# IO.net
KiCad netlist of a schematic drawn in Altium Designer
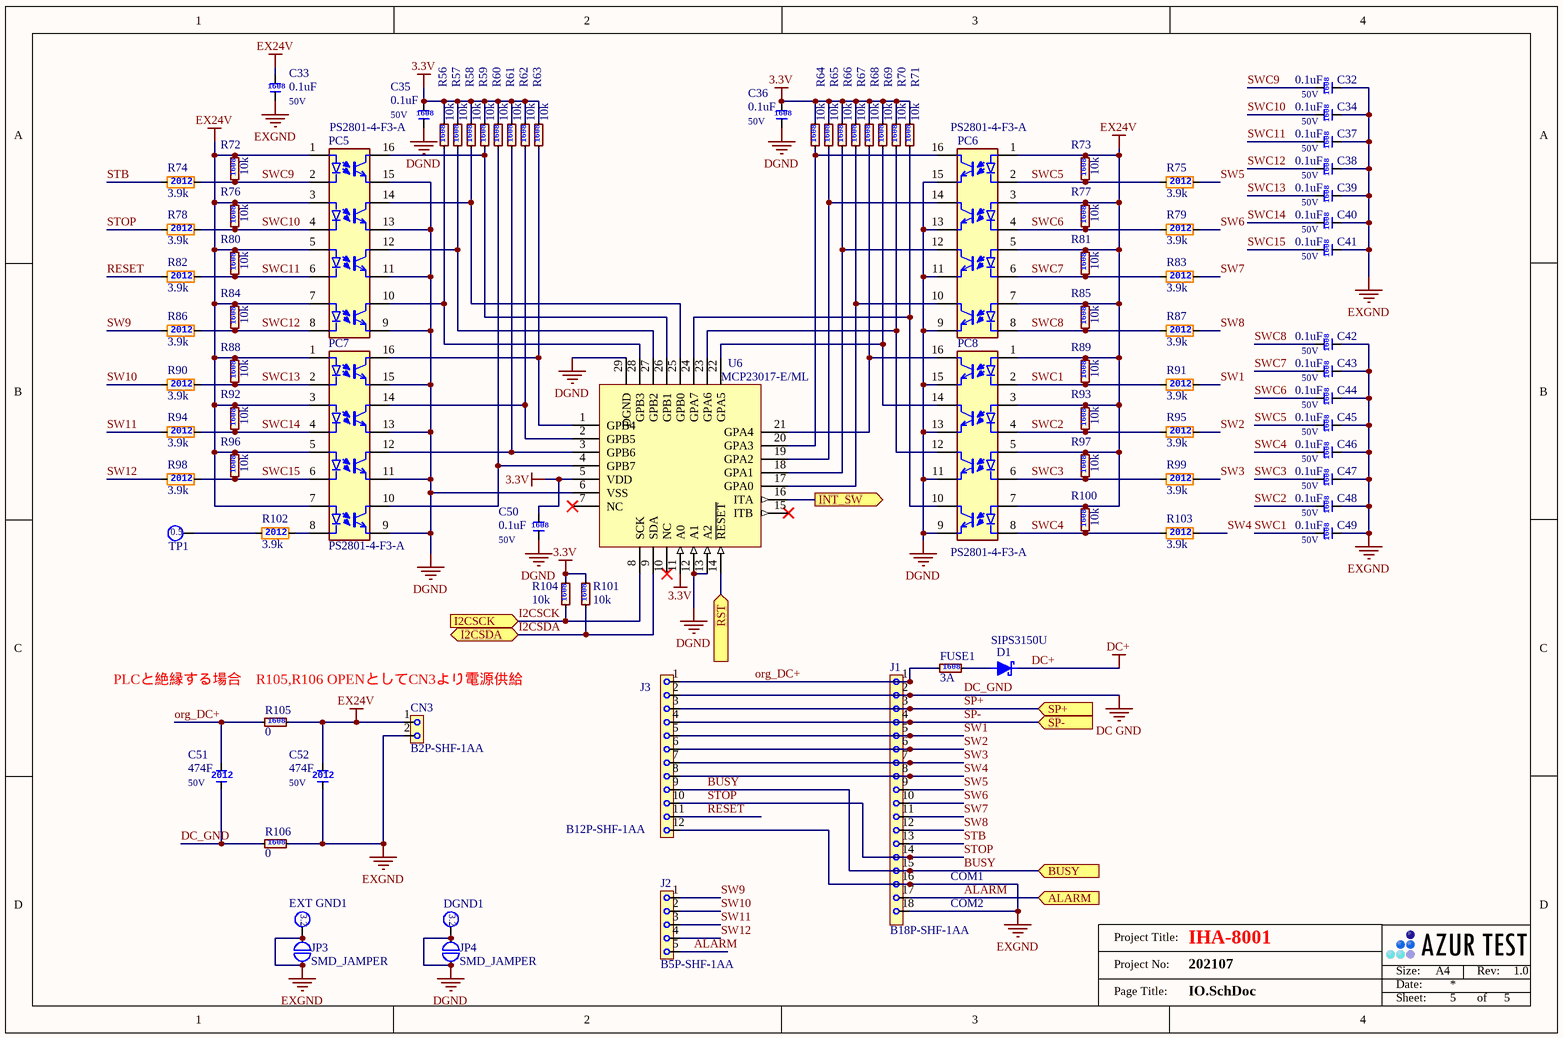
[diagram p0: IO.SchDoc]

(export (version "E")
  (design (tool "Eeschema 10.0.6"))
  (components
    (comp (ref "C32")
      (value "CGA3E2X7R1H104K080AA")
      (footprint "C1608")
      (description "セラコン1608サイズ")
      (fields (field (name "TAG") "0.1uF") (field (name "VOLTAGE") "50V"))
      (libsource (lib "Audio Prj") (part "C1608"))
    )
    (comp (ref "C33")
      (value "CGA3E2X7R1H104K080AA")
      (footprint "C1608")
      (description "セラコン1608サイズ")
      (fields (field (name "TAG") "0.1uF") (field (name "VOLTAGE") "50V"))
      (libsource (lib "Audio Prj") (part "C1608"))
    )
    (comp (ref "C34")
      (value "CGA3E2X7R1H104K080AA")
      (footprint "C1608")
      (description "セラコン1608サイズ")
      (fields (field (name "TAG") "0.1uF") (field (name "VOLTAGE") "50V"))
      (libsource (lib "Audio Prj") (part "C1608"))
    )
    (comp (ref "C35")
      (value "CGA3E2X7R1H104K080AA")
      (footprint "C1608")
      (description "セラコン1608サイズ")
      (fields (field (name "TAG") "0.1uF") (field (name "VOLTAGE") "50V"))
      (libsource (lib "Audio Prj") (part "C1608"))
    )
    (comp (ref "C36")
      (value "CGA3E2X7R1H104K080AA")
      (footprint "C1608")
      (description "セラコン1608サイズ")
      (fields (field (name "TAG") "0.1uF") (field (name "VOLTAGE") "50V"))
      (libsource (lib "Audio Prj") (part "C1608"))
    )
    (comp (ref "C37")
      (value "CGA3E2X7R1H104K080AA")
      (footprint "C1608")
      (description "セラコン1608サイズ")
      (fields (field (name "TAG") "0.1uF") (field (name "VOLTAGE") "50V"))
      (libsource (lib "Audio Prj") (part "C1608"))
    )
    (comp (ref "C38")
      (value "CGA3E2X7R1H104K080AA")
      (footprint "C1608")
      (description "セラコン1608サイズ")
      (fields (field (name "TAG") "0.1uF") (field (name "VOLTAGE") "50V"))
      (libsource (lib "Audio Prj") (part "C1608"))
    )
    (comp (ref "C39")
      (value "CGA3E2X7R1H104K080AA")
      (footprint "C1608")
      (description "セラコン1608サイズ")
      (fields (field (name "TAG") "0.1uF") (field (name "VOLTAGE") "50V"))
      (libsource (lib "Audio Prj") (part "C1608"))
    )
    (comp (ref "C40")
      (value "CGA3E2X7R1H104K080AA")
      (footprint "C1608")
      (description "セラコン1608サイズ")
      (fields (field (name "TAG") "0.1uF") (field (name "VOLTAGE") "50V"))
      (libsource (lib "Audio Prj") (part "C1608"))
    )
    (comp (ref "C41")
      (value "CGA3E2X7R1H104K080AA")
      (footprint "C1608")
      (description "セラコン1608サイズ")
      (fields (field (name "TAG") "0.1uF") (field (name "VOLTAGE") "50V"))
      (libsource (lib "Audio Prj") (part "C1608"))
    )
    (comp (ref "C42")
      (value "CGA3E2X7R1H104K080AA")
      (footprint "C1608")
      (description "セラコン1608サイズ")
      (fields (field (name "TAG") "0.1uF") (field (name "VOLTAGE") "50V"))
      (libsource (lib "Audio Prj") (part "C1608"))
    )
    (comp (ref "C43")
      (value "CGA3E2X7R1H104K080AA")
      (footprint "C1608")
      (description "セラコン1608サイズ")
      (fields (field (name "TAG") "0.1uF") (field (name "VOLTAGE") "50V"))
      (libsource (lib "Audio Prj") (part "C1608"))
    )
    (comp (ref "C44")
      (value "CGA3E2X7R1H104K080AA")
      (footprint "C1608")
      (description "セラコン1608サイズ")
      (fields (field (name "TAG") "0.1uF") (field (name "VOLTAGE") "50V"))
      (libsource (lib "Audio Prj") (part "C1608"))
    )
    (comp (ref "C45")
      (value "CGA3E2X7R1H104K080AA")
      (footprint "C1608")
      (description "セラコン1608サイズ")
      (fields (field (name "TAG") "0.1uF") (field (name "VOLTAGE") "50V"))
      (libsource (lib "Audio Prj") (part "C1608"))
    )
    (comp (ref "C46")
      (value "CGA3E2X7R1H104K080AA")
      (footprint "C1608")
      (description "セラコン1608サイズ")
      (fields (field (name "TAG") "0.1uF") (field (name "VOLTAGE") "50V"))
      (libsource (lib "Audio Prj") (part "C1608"))
    )
    (comp (ref "C47")
      (value "CGA3E2X7R1H104K080AA")
      (footprint "C1608")
      (description "セラコン1608サイズ")
      (fields (field (name "TAG") "0.1uF") (field (name "VOLTAGE") "50V"))
      (libsource (lib "Audio Prj") (part "C1608"))
    )
    (comp (ref "C48")
      (value "CGA3E2X7R1H104K080AA")
      (footprint "C1608")
      (description "セラコン1608サイズ")
      (fields (field (name "TAG") "0.1uF") (field (name "VOLTAGE") "50V"))
      (libsource (lib "Audio Prj") (part "C1608"))
    )
    (comp (ref "C49")
      (value "CGA3E2X7R1H104K080AA")
      (footprint "C1608")
      (description "セラコン1608サイズ")
      (fields (field (name "TAG") "0.1uF") (field (name "VOLTAGE") "50V"))
      (libsource (lib "Audio Prj") (part "C1608"))
    )
    (comp (ref "C50")
      (value "CGA3E2X7R1H104K080AA")
      (footprint "C1608")
      (description "セラコン1608サイズ")
      (fields (field (name "TAG") "0.1uF") (field (name "VOLTAGE") "50V"))
      (libsource (lib "Audio Prj") (part "C1608"))
    )
    (comp (ref "C51")
      (value "GRM21BR71H474MA88")
      (footprint "C2012")
      (description "セラコン2012サイズ")
      (fields (field (name "TAG") "474F") (field (name "VOLTAGE") "50V"))
      (libsource (lib "Audio Prj") (part "C2012"))
    )
    (comp (ref "C52")
      (value "GRM21BR71H474MA88")
      (footprint "C2012")
      (description "セラコン2012サイズ")
      (fields (field (name "TAG") "474F") (field (name "VOLTAGE") "50V"))
      (libsource (lib "Audio Prj") (part "C2012"))
    )
    (comp (ref "CN3")
      (value "B2P-SHF-1AA")
      (footprint "B2P-SHF-1AA")
      (description "雄,ストレート,1列2ピン")
      (libsource (lib "Audio Prj") (part "B2P-SHF-1AA"))
    )
    (comp (ref "D1")
      (value "SIPS3150U")
      (footprint "DO-214AA")
      (description "Schottky Rectifier")
      (fields (field (name "VOLTAGE") "150V"))
      (libsource (lib "Audio Prj") (part "Diode SMB 5.4x4.3"))
    )
    (comp (ref "DGND1")
      (value "TP3.2mm")
      (footprint "TP3.2mm")
      (description "Test-Point 3.2mm")
      (libsource (lib "Audio Prj") (part "TP3.2mm"))
    )
    (comp (ref "EXT GND1")
      (value "TP3.2mm")
      (footprint "TP3.2mm")
      (description "Test-Point 3.2mm")
      (libsource (lib "Audio Prj") (part "TP3.2mm"))
    )
    (comp (ref "FUSE1")
      (value "ERB-RE3R00V")
      (footprint "R1608")
      (description "3A 1608サイズ")
      (fields (field (name "TAG") "3A"))
      (libsource (lib "") (part "TF1608_1"))
    )
    (comp (ref "J1")
      (value "B18P-SHF-1AA")
      (footprint "B18P-SHF-1AA")
      (description "雄,ストレート,1列12ピン PCB")
      (libsource (lib "Audio Prj") (part "B18P-SHF-1AA"))
    )
    (comp (ref "J2")
      (value "B5P-SHF-1AA")
      (footprint "B5P-SHF-1AA")
      (description "雄,ストレート,1列3ピン")
      (libsource (lib "Audio Prj") (part "B5P-SHF-1AA"))
    )
    (comp (ref "J3")
      (value "B12P-SHF-1AA")
      (footprint "B12P-SHF-1AA")
      (description "雄,ストレート,1列12ピン PCB")
      (libsource (lib "Audio Prj") (part "B12P-SHF-1AA"))
    )
    (comp (ref "JP3")
      (value "SMD_JAMPER")
      (footprint "SMD_JAMPER -Cut")
      (libsource (lib "Audio Prj") (part "SMD_JAMPER"))
    )
    (comp (ref "JP4")
      (value "SMD_JAMPER")
      (footprint "SMD_JAMPER -Cut")
      (libsource (lib "Audio") (part "SMD_JAMPER"))
    )
    (comp (ref "PC5")
      (value "PS2801-4-F3-A")
      (footprint "SO16")
      (description "4 Channel 16-SO")
      (libsource (lib "Audio Prj") (part "TLP293-4"))
    )
    (comp (ref "PC6")
      (value "PS2801-4-F3-A")
      (footprint "SO16")
      (description "4 Channel 16-SO")
      (libsource (lib "Audio Prj") (part "TLP293-4"))
    )
    (comp (ref "PC7")
      (value "PS2801-4-F3-A")
      (footprint "SO16")
      (description "4 Channel 16-SO")
      (libsource (lib "Audio Prj") (part "TLP293-4"))
    )
    (comp (ref "PC8")
      (value "PS2801-4-F3-A")
      (footprint "SO16")
      (description "4 Channel 16-SO")
      (libsource (lib "Audio Prj") (part "TLP293-4"))
    )
    (comp (ref "R56")
      (value "ERJ-PA3F1002V")
      (footprint "R1608")
      (description "厚膜チップ抵抗1608サイズ")
      (fields (field (name "TAG") "10k"))
      (libsource (lib "Audio Prj") (part "TF1608"))
    )
    (comp (ref "R57")
      (value "ERJ-PA3F1002V")
      (footprint "R1608")
      (description "厚膜チップ抵抗1608サイズ")
      (fields (field (name "TAG") "10k"))
      (libsource (lib "Audio Prj") (part "TF1608"))
    )
    (comp (ref "R58")
      (value "ERJ-PA3F1002V")
      (footprint "R1608")
      (description "厚膜チップ抵抗1608サイズ")
      (fields (field (name "TAG") "10k"))
      (libsource (lib "Audio Prj") (part "TF1608"))
    )
    (comp (ref "R59")
      (value "ERJ-PA3F1002V")
      (footprint "R1608")
      (description "厚膜チップ抵抗1608サイズ")
      (fields (field (name "TAG") "10k"))
      (libsource (lib "Audio Prj") (part "TF1608"))
    )
    (comp (ref "R60")
      (value "ERJ-PA3F1002V")
      (footprint "R1608")
      (description "厚膜チップ抵抗1608サイズ")
      (fields (field (name "TAG") "10k"))
      (libsource (lib "Audio Prj") (part "TF1608"))
    )
    (comp (ref "R61")
      (value "ERJ-PA3F1002V")
      (footprint "R1608")
      (description "厚膜チップ抵抗1608サイズ")
      (fields (field (name "TAG") "10k"))
      (libsource (lib "Audio Prj") (part "TF1608"))
    )
    (comp (ref "R62")
      (value "ERJ-PA3F1002V")
      (footprint "R1608")
      (description "厚膜チップ抵抗1608サイズ")
      (fields (field (name "TAG") "10k"))
      (libsource (lib "Audio Prj") (part "TF1608"))
    )
    (comp (ref "R63")
      (value "ERJ-PA3F1002V")
      (footprint "R1608")
      (description "厚膜チップ抵抗1608サイズ")
      (fields (field (name "TAG") "10k"))
      (libsource (lib "Audio Prj") (part "TF1608"))
    )
    (comp (ref "R64")
      (value "ERJ-PA3F1002V")
      (footprint "R1608")
      (description "厚膜チップ抵抗1608サイズ")
      (fields (field (name "TAG") "10k"))
      (libsource (lib "Audio Prj") (part "TF1608"))
    )
    (comp (ref "R65")
      (value "ERJ-PA3F1002V")
      (footprint "R1608")
      (description "厚膜チップ抵抗1608サイズ")
      (fields (field (name "TAG") "10k"))
      (libsource (lib "Audio Prj") (part "TF1608"))
    )
    (comp (ref "R66")
      (value "ERJ-PA3F1002V")
      (footprint "R1608")
      (description "厚膜チップ抵抗1608サイズ")
      (fields (field (name "TAG") "10k"))
      (libsource (lib "Audio Prj") (part "TF1608"))
    )
    (comp (ref "R67")
      (value "ERJ-PA3F1002V")
      (footprint "R1608")
      (description "厚膜チップ抵抗1608サイズ")
      (fields (field (name "TAG") "10k"))
      (libsource (lib "Audio Prj") (part "TF1608"))
    )
    (comp (ref "R68")
      (value "ERJ-PA3F1002V")
      (footprint "R1608")
      (description "厚膜チップ抵抗1608サイズ")
      (fields (field (name "TAG") "10k"))
      (libsource (lib "Audio Prj") (part "TF1608"))
    )
    (comp (ref "R69")
      (value "ERJ-PA3F1002V")
      (footprint "R1608")
      (description "厚膜チップ抵抗1608サイズ")
      (fields (field (name "TAG") "10k"))
      (libsource (lib "Audio Prj") (part "TF1608"))
    )
    (comp (ref "R70")
      (value "ERJ-PA3F1002V")
      (footprint "R1608")
      (description "厚膜チップ抵抗1608サイズ")
      (fields (field (name "TAG") "10k"))
      (libsource (lib "Audio Prj") (part "TF1608"))
    )
    (comp (ref "R71")
      (value "ERJ-PA3F1002V")
      (footprint "R1608")
      (description "厚膜チップ抵抗1608サイズ")
      (fields (field (name "TAG") "10k"))
      (libsource (lib "Audio Prj") (part "TF1608"))
    )
    (comp (ref "R72")
      (value "ERJ-PA3F1002V")
      (footprint "R1608")
      (description "厚膜チップ抵抗1608サイズ")
      (fields (field (name "TAG") "10k"))
      (libsource (lib "Audio Prj") (part "TF1608"))
    )
    (comp (ref "R73")
      (value "ERJ-PA3F1002V")
      (footprint "R1608")
      (description "厚膜チップ抵抗1608サイズ")
      (fields (field (name "TAG") "10k"))
      (libsource (lib "Audio Prj") (part "TF1608"))
    )
    (comp (ref "R74")
      (value "RK73B2ATTD392J")
      (footprint "R2012")
      (description "薄膜チップ抵抗2012サイズ")
      (fields (field (name "TAG") "3.9k"))
      (libsource (lib "Audio Prj") (part "MF2012"))
    )
    (comp (ref "R75")
      (value "RK73B2ATTD392J")
      (footprint "R2012")
      (description "薄膜チップ抵抗2012サイズ")
      (fields (field (name "TAG") "3.9k"))
      (libsource (lib "Audio Prj") (part "MF2012"))
    )
    (comp (ref "R76")
      (value "ERJ-PA3F1002V")
      (footprint "R1608")
      (description "厚膜チップ抵抗1608サイズ")
      (fields (field (name "TAG") "10k"))
      (libsource (lib "Audio Prj") (part "TF1608"))
    )
    (comp (ref "R77")
      (value "ERJ-PA3F1002V")
      (footprint "R1608")
      (description "厚膜チップ抵抗1608サイズ")
      (fields (field (name "TAG") "10k"))
      (libsource (lib "Audio Prj") (part "TF1608"))
    )
    (comp (ref "R78")
      (value "RK73B2ATTD392J")
      (footprint "R2012")
      (description "薄膜チップ抵抗2012サイズ")
      (fields (field (name "TAG") "3.9k"))
      (libsource (lib "Audio Prj") (part "MF2012"))
    )
    (comp (ref "R79")
      (value "RK73B2ATTD392J")
      (footprint "R2012")
      (description "薄膜チップ抵抗2012サイズ")
      (fields (field (name "TAG") "3.9k"))
      (libsource (lib "Audio Prj") (part "MF2012"))
    )
    (comp (ref "R80")
      (value "ERJ-PA3F1002V")
      (footprint "R1608")
      (description "厚膜チップ抵抗1608サイズ")
      (fields (field (name "TAG") "10k"))
      (libsource (lib "Audio Prj") (part "TF1608"))
    )
    (comp (ref "R81")
      (value "ERJ-PA3F1002V")
      (footprint "R1608")
      (description "厚膜チップ抵抗1608サイズ")
      (fields (field (name "TAG") "10k"))
      (libsource (lib "Audio Prj") (part "TF1608"))
    )
    (comp (ref "R82")
      (value "RK73B2ATTD392J")
      (footprint "R2012")
      (description "薄膜チップ抵抗2012サイズ")
      (fields (field (name "TAG") "3.9k"))
      (libsource (lib "Audio Prj") (part "MF2012"))
    )
    (comp (ref "R83")
      (value "RK73B2ATTD392J")
      (footprint "R2012")
      (description "薄膜チップ抵抗2012サイズ")
      (fields (field (name "TAG") "3.9k"))
      (libsource (lib "Audio Prj") (part "MF2012"))
    )
    (comp (ref "R84")
      (value "ERJ-PA3F1002V")
      (footprint "R1608")
      (description "厚膜チップ抵抗1608サイズ")
      (fields (field (name "TAG") "10k"))
      (libsource (lib "Audio Prj") (part "TF1608"))
    )
    (comp (ref "R85")
      (value "ERJ-PA3F1002V")
      (footprint "R1608")
      (description "厚膜チップ抵抗1608サイズ")
      (fields (field (name "TAG") "10k"))
      (libsource (lib "Audio Prj") (part "TF1608"))
    )
    (comp (ref "R86")
      (value "RK73B2ATTD392J")
      (footprint "R2012")
      (description "薄膜チップ抵抗2012サイズ")
      (fields (field (name "TAG") "3.9k"))
      (libsource (lib "Audio Prj") (part "MF2012"))
    )
    (comp (ref "R87")
      (value "RK73B2ATTD392J")
      (footprint "R2012")
      (description "薄膜チップ抵抗2012サイズ")
      (fields (field (name "TAG") "3.9k"))
      (libsource (lib "Audio Prj") (part "MF2012"))
    )
    (comp (ref "R88")
      (value "ERJ-PA3F1002V")
      (footprint "R1608")
      (description "厚膜チップ抵抗1608サイズ")
      (fields (field (name "TAG") "10k"))
      (libsource (lib "Audio Prj") (part "TF1608"))
    )
    (comp (ref "R89")
      (value "ERJ-PA3F1002V")
      (footprint "R1608")
      (description "厚膜チップ抵抗1608サイズ")
      (fields (field (name "TAG") "10k"))
      (libsource (lib "Audio Prj") (part "TF1608"))
    )
    (comp (ref "R90")
      (value "RK73B2ATTD392J")
      (footprint "R2012")
      (description "薄膜チップ抵抗2012サイズ")
      (fields (field (name "TAG") "3.9k"))
      (libsource (lib "Audio Prj") (part "MF2012"))
    )
    (comp (ref "R91")
      (value "RK73B2ATTD392J")
      (footprint "R2012")
      (description "薄膜チップ抵抗2012サイズ")
      (fields (field (name "TAG") "3.9k"))
      (libsource (lib "Audio Prj") (part "MF2012"))
    )
    (comp (ref "R92")
      (value "ERJ-PA3F1002V")
      (footprint "R1608")
      (description "厚膜チップ抵抗1608サイズ")
      (fields (field (name "TAG") "10k"))
      (libsource (lib "Audio Prj") (part "TF1608"))
    )
    (comp (ref "R93")
      (value "ERJ-PA3F1002V")
      (footprint "R1608")
      (description "厚膜チップ抵抗1608サイズ")
      (fields (field (name "TAG") "10k"))
      (libsource (lib "Audio Prj") (part "TF1608"))
    )
    (comp (ref "R94")
      (value "RK73B2ATTD392J")
      (footprint "R2012")
      (description "薄膜チップ抵抗2012サイズ")
      (fields (field (name "TAG") "3.9k"))
      (libsource (lib "Audio Prj") (part "MF2012"))
    )
    (comp (ref "R95")
      (value "RK73B2ATTD392J")
      (footprint "R2012")
      (description "薄膜チップ抵抗2012サイズ")
      (fields (field (name "TAG") "3.9k"))
      (libsource (lib "Audio Prj") (part "MF2012"))
    )
    (comp (ref "R96")
      (value "ERJ-PA3F1002V")
      (footprint "R1608")
      (description "厚膜チップ抵抗1608サイズ")
      (fields (field (name "TAG") "10k"))
      (libsource (lib "Audio Prj") (part "TF1608"))
    )
    (comp (ref "R97")
      (value "ERJ-PA3F1002V")
      (footprint "R1608")
      (description "厚膜チップ抵抗1608サイズ")
      (fields (field (name "TAG") "10k"))
      (libsource (lib "Audio Prj") (part "TF1608"))
    )
    (comp (ref "R98")
      (value "RK73B2ATTD392J")
      (footprint "R2012")
      (description "薄膜チップ抵抗2012サイズ")
      (fields (field (name "TAG") "3.9k"))
      (libsource (lib "Audio Prj") (part "MF2012"))
    )
    (comp (ref "R99")
      (value "RK73B2ATTD392J")
      (footprint "R2012")
      (description "薄膜チップ抵抗2012サイズ")
      (fields (field (name "TAG") "3.9k"))
      (libsource (lib "Audio Prj") (part "MF2012"))
    )
    (comp (ref "R100")
      (value "ERJ-PA3F1002V")
      (footprint "R1608")
      (description "厚膜チップ抵抗1608サイズ")
      (fields (field (name "TAG") "10k"))
      (libsource (lib "Audio Prj") (part "TF1608"))
    )
    (comp (ref "R101")
      (value "ERJ-PA3F1002V")
      (footprint "R1608")
      (description "厚膜チップ抵抗1608サイズ")
      (fields (field (name "TAG") "10k"))
      (libsource (lib "Audio Prj") (part "TF1608"))
    )
    (comp (ref "R102")
      (value "RK73B2ATTD392J")
      (footprint "R2012")
      (description "薄膜チップ抵抗2012サイズ")
      (fields (field (name "TAG") "3.9k"))
      (libsource (lib "Audio Prj") (part "MF2012"))
    )
    (comp (ref "R103")
      (value "RK73B2ATTD392J")
      (footprint "R2012")
      (description "薄膜チップ抵抗2012サイズ")
      (fields (field (name "TAG") "3.9k"))
      (libsource (lib "Audio Prj") (part "MF2012"))
    )
    (comp (ref "R104")
      (value "ERJ-PA3F1002V")
      (footprint "R1608")
      (description "厚膜チップ抵抗1608サイズ")
      (fields (field (name "TAG") "10k"))
      (libsource (lib "Audio Prj") (part "TF1608"))
    )
    (comp (ref "R105")
      (value "RK73Z1JTTD")
      (footprint "R1608")
      (description "厚膜チップ抵抗1608サイズ")
      (fields (field (name "TAG") "0"))
      (libsource (lib "") (part "TF1608_1"))
    )
    (comp (ref "R106")
      (value "RK73Z1JTTD")
      (footprint "R1608")
      (description "厚膜チップ抵抗1608サイズ")
      (fields (field (name "TAG") "0"))
      (libsource (lib "") (part "TF1608_1"))
    )
    (comp (ref "TP1")
      (value "TP0.5mm")
      (footprint "TP0.5mm")
      (description "Test-Point 0.5mm")
      (libsource (lib "Audio") (part "TP0.5mm"))
    )
    (comp (ref "U6")
      (value "MCP23017-E/ML")
      (footprint "QFN28")
      (description "I/O Expander 16 SPI 10MHz 28-SOIC")
      (libsource (lib "Audio Prj") (part "MCP23017-E/ML"))
    )
  )
  (nets
    (net (code "1") (name "/ALARM") (class "Default")
      (node (ref "J1") (pin "17") (pinfunction "17_17") (pintype "passive"))
      (node (ref "J2") (pin "5") (pinfunction "5_5") (pintype "passive"))
    )
    (net (code "2") (name "/BUSY") (class "Default")
      (node (ref "J1") (pin "15") (pinfunction "15_15") (pintype "passive"))
      (node (ref "J3") (pin "9") (pinfunction "9_9") (pintype "passive"))
    )
    (net (code "3") (name "/I2CSCK") (class "Default")
      (node (ref "R104") (pin "1") (pinfunction "1_1") (pintype "passive"))
      (node (ref "U6") (pin "8") (pinfunction "SCK_8") (pintype "passive"))
    )
    (net (code "4") (name "/I2CSDA") (class "Default")
      (node (ref "R101") (pin "1") (pinfunction "1_1") (pintype "passive"))
      (node (ref "U6") (pin "9") (pinfunction "SDA_9") (pintype "passive"))
    )
    (net (code "5") (name "/INT_SW") (class "Default")
      (node (ref "U6") (pin "16") (pinfunction "ITA_16") (pintype "output"))
    )
    (net (code "6") (name "/RESET") (class "Default")
      (node (ref "J3") (pin "11") (pinfunction "11_11") (pintype "passive"))
      (node (ref "R82") (pin "1") (pinfunction "1_1") (pintype "passive"))
    )
    (net (code "7") (name "/RST") (class "Default")
      (node (ref "U6") (pin "14") (pinfunction "~{RESET}_14") (pintype "input"))
    )
    (net (code "8") (name "/SP+") (class "Default")
      (node (ref "J1") (pin "3") (pinfunction "3_3") (pintype "passive"))
      (node (ref "J3") (pin "3") (pinfunction "3_3") (pintype "passive"))
    )
    (net (code "9") (name "/SP-") (class "Default")
      (node (ref "J1") (pin "4") (pinfunction "4_4") (pintype "passive"))
      (node (ref "J3") (pin "4") (pinfunction "4_4") (pintype "passive"))
    )
    (net (code "10") (name "/STB") (class "Default")
      (node (ref "J1") (pin "13") (pinfunction "13_13") (pintype "passive"))
      (node (ref "R74") (pin "1") (pinfunction "1_1") (pintype "passive"))
    )
    (net (code "11") (name "/STOP") (class "Default")
      (node (ref "J1") (pin "14") (pinfunction "14_14") (pintype "passive"))
      (node (ref "J3") (pin "10") (pinfunction "10_10") (pintype "passive"))
      (node (ref "R78") (pin "1") (pinfunction "1_1") (pintype "passive"))
    )
    (net (code "12") (name "/SW1") (class "Default")
      (node (ref "J1") (pin "5") (pinfunction "5_5") (pintype "passive"))
      (node (ref "J3") (pin "5") (pinfunction "5_5") (pintype "passive"))
      (node (ref "R91") (pin "2") (pinfunction "2_2") (pintype "passive"))
    )
    (net (code "13") (name "/SW2") (class "Default")
      (node (ref "J1") (pin "6") (pinfunction "6_6") (pintype "passive"))
      (node (ref "J3") (pin "6") (pinfunction "6_6") (pintype "passive"))
      (node (ref "R95") (pin "2") (pinfunction "2_2") (pintype "passive"))
    )
    (net (code "14") (name "/SW3") (class "Default")
      (node (ref "J1") (pin "7") (pinfunction "7_7") (pintype "passive"))
      (node (ref "J3") (pin "7") (pinfunction "7_7") (pintype "passive"))
      (node (ref "R99") (pin "2") (pinfunction "2_2") (pintype "passive"))
    )
    (net (code "15") (name "/SW4") (class "Default")
      (node (ref "J1") (pin "8") (pinfunction "8_8") (pintype "passive"))
      (node (ref "J3") (pin "8") (pinfunction "8_8") (pintype "passive"))
      (node (ref "R103") (pin "2") (pinfunction "2_2") (pintype "passive"))
    )
    (net (code "16") (name "/SW5") (class "Default")
      (node (ref "J1") (pin "9") (pinfunction "9_9") (pintype "passive"))
      (node (ref "R75") (pin "2") (pinfunction "2_2") (pintype "passive"))
    )
    (net (code "17") (name "/SW6") (class "Default")
      (node (ref "J1") (pin "10") (pinfunction "10_10") (pintype "passive"))
      (node (ref "R79") (pin "2") (pinfunction "2_2") (pintype "passive"))
    )
    (net (code "18") (name "/SW7") (class "Default")
      (node (ref "J1") (pin "11") (pinfunction "11_11") (pintype "passive"))
      (node (ref "R83") (pin "2") (pinfunction "2_2") (pintype "passive"))
    )
    (net (code "19") (name "/SW8") (class "Default")
      (node (ref "J1") (pin "12") (pinfunction "12_12") (pintype "passive"))
      (node (ref "R87") (pin "2") (pinfunction "2_2") (pintype "passive"))
    )
    (net (code "20") (name "/SW9") (class "Default")
      (node (ref "J2") (pin "1") (pinfunction "1_1") (pintype "passive"))
      (node (ref "R86") (pin "1") (pinfunction "1_1") (pintype "passive"))
    )
    (net (code "21") (name "/SW10") (class "Default")
      (node (ref "J2") (pin "2") (pinfunction "2_2") (pintype "passive"))
      (node (ref "R90") (pin "1") (pinfunction "1_1") (pintype "passive"))
    )
    (net (code "22") (name "/SW11") (class "Default")
      (node (ref "J2") (pin "3") (pinfunction "3_3") (pintype "passive"))
      (node (ref "R94") (pin "1") (pinfunction "1_1") (pintype "passive"))
    )
    (net (code "23") (name "/SW12") (class "Default")
      (node (ref "J2") (pin "4") (pinfunction "4_4") (pintype "passive"))
      (node (ref "R98") (pin "1") (pinfunction "1_1") (pintype "passive"))
    )
    (net (code "24") (name "/SWC1") (class "Default")
      (node (ref "C49") (pin "2") (pinfunction "2_2") (pintype "passive"))
      (node (ref "PC8") (pin "2") (pinfunction "K-LED_2") (pintype "passive"))
      (node (ref "R89") (pin "1") (pinfunction "1_1") (pintype "passive"))
      (node (ref "R91") (pin "1") (pinfunction "1_1") (pintype "passive"))
    )
    (net (code "25") (name "/SWC2") (class "Default")
      (node (ref "C48") (pin "2") (pinfunction "2_2") (pintype "passive"))
      (node (ref "PC8") (pin "4") (pinfunction "K-LED_4") (pintype "passive"))
      (node (ref "R93") (pin "1") (pinfunction "1_1") (pintype "passive"))
      (node (ref "R95") (pin "1") (pinfunction "1_1") (pintype "passive"))
    )
    (net (code "26") (name "/SWC3") (class "Default")
      (node (ref "C47") (pin "2") (pinfunction "2_2") (pintype "passive"))
      (node (ref "PC8") (pin "6") (pinfunction "K-LED_6") (pintype "passive"))
      (node (ref "R97") (pin "1") (pinfunction "1_1") (pintype "passive"))
      (node (ref "R99") (pin "1") (pinfunction "1_1") (pintype "passive"))
    )
    (net (code "27") (name "/SWC4") (class "Default")
      (node (ref "C46") (pin "2") (pinfunction "2_2") (pintype "passive"))
      (node (ref "PC8") (pin "8") (pinfunction "K-LED_8") (pintype "passive"))
      (node (ref "R100") (pin "1") (pinfunction "1_1") (pintype "passive"))
      (node (ref "R103") (pin "1") (pinfunction "1_1") (pintype "passive"))
    )
    (net (code "28") (name "/SWC5") (class "Default")
      (node (ref "C45") (pin "2") (pinfunction "2_2") (pintype "passive"))
      (node (ref "PC6") (pin "2") (pinfunction "K-LED_2") (pintype "passive"))
      (node (ref "R73") (pin "1") (pinfunction "1_1") (pintype "passive"))
      (node (ref "R75") (pin "1") (pinfunction "1_1") (pintype "passive"))
    )
    (net (code "29") (name "/SWC6") (class "Default")
      (node (ref "C44") (pin "2") (pinfunction "2_2") (pintype "passive"))
      (node (ref "PC6") (pin "4") (pinfunction "K-LED_4") (pintype "passive"))
      (node (ref "R77") (pin "1") (pinfunction "1_1") (pintype "passive"))
      (node (ref "R79") (pin "1") (pinfunction "1_1") (pintype "passive"))
    )
    (net (code "30") (name "/SWC7") (class "Default")
      (node (ref "C43") (pin "2") (pinfunction "2_2") (pintype "passive"))
      (node (ref "PC6") (pin "6") (pinfunction "K-LED_6") (pintype "passive"))
      (node (ref "R81") (pin "1") (pinfunction "1_1") (pintype "passive"))
      (node (ref "R83") (pin "1") (pinfunction "1_1") (pintype "passive"))
    )
    (net (code "31") (name "/SWC8") (class "Default")
      (node (ref "C42") (pin "2") (pinfunction "2_2") (pintype "passive"))
      (node (ref "PC6") (pin "8") (pinfunction "K-LED_8") (pintype "passive"))
      (node (ref "R85") (pin "1") (pinfunction "1_1") (pintype "passive"))
      (node (ref "R87") (pin "1") (pinfunction "1_1") (pintype "passive"))
    )
    (net (code "32") (name "/SWC9") (class "Default")
      (node (ref "C32") (pin "2") (pinfunction "2_2") (pintype "passive"))
      (node (ref "PC5") (pin "2") (pinfunction "K-LED_2") (pintype "passive"))
      (node (ref "R72") (pin "1") (pinfunction "1_1") (pintype "passive"))
      (node (ref "R74") (pin "2") (pinfunction "2_2") (pintype "passive"))
    )
    (net (code "33") (name "/SWC10") (class "Default")
      (node (ref "C34") (pin "2") (pinfunction "2_2") (pintype "passive"))
      (node (ref "PC5") (pin "4") (pinfunction "K-LED_4") (pintype "passive"))
      (node (ref "R76") (pin "1") (pinfunction "1_1") (pintype "passive"))
      (node (ref "R78") (pin "2") (pinfunction "2_2") (pintype "passive"))
    )
    (net (code "34") (name "/SWC11") (class "Default")
      (node (ref "C37") (pin "2") (pinfunction "2_2") (pintype "passive"))
      (node (ref "PC5") (pin "6") (pinfunction "K-LED_6") (pintype "passive"))
      (node (ref "R80") (pin "1") (pinfunction "1_1") (pintype "passive"))
      (node (ref "R82") (pin "2") (pinfunction "2_2") (pintype "passive"))
    )
    (net (code "35") (name "/SWC12") (class "Default")
      (node (ref "C38") (pin "2") (pinfunction "2_2") (pintype "passive"))
      (node (ref "PC5") (pin "8") (pinfunction "K-LED_8") (pintype "passive"))
      (node (ref "R84") (pin "1") (pinfunction "1_1") (pintype "passive"))
      (node (ref "R86") (pin "2") (pinfunction "2_2") (pintype "passive"))
    )
    (net (code "36") (name "/SWC13") (class "Default")
      (node (ref "C39") (pin "2") (pinfunction "2_2") (pintype "passive"))
      (node (ref "PC7") (pin "2") (pinfunction "K-LED_2") (pintype "passive"))
      (node (ref "R88") (pin "1") (pinfunction "1_1") (pintype "passive"))
      (node (ref "R90") (pin "2") (pinfunction "2_2") (pintype "passive"))
    )
    (net (code "37") (name "/SWC14") (class "Default")
      (node (ref "C40") (pin "2") (pinfunction "2_2") (pintype "passive"))
      (node (ref "PC7") (pin "4") (pinfunction "K-LED_4") (pintype "passive"))
      (node (ref "R92") (pin "1") (pinfunction "1_1") (pintype "passive"))
      (node (ref "R94") (pin "2") (pinfunction "2_2") (pintype "passive"))
    )
    (net (code "38") (name "/SWC15") (class "Default")
      (node (ref "C41") (pin "2") (pinfunction "2_2") (pintype "passive"))
      (node (ref "PC7") (pin "6") (pinfunction "K-LED_6") (pintype "passive"))
      (node (ref "R96") (pin "1") (pinfunction "1_1") (pintype "passive"))
      (node (ref "R98") (pin "2") (pinfunction "2_2") (pintype "passive"))
    )
    (net (code "39") (name "/org_DC+") (class "Default")
      (node (ref "C51") (pin "2") (pinfunction "2_2") (pintype "passive"))
      (node (ref "FUSE1") (pin "1") (pinfunction "1_1") (pintype "passive"))
      (node (ref "J1") (pin "1") (pinfunction "1_1") (pintype "passive"))
      (node (ref "J3") (pin "1") (pinfunction "1_1") (pintype "passive"))
      (node (ref "R105") (pin "1") (pinfunction "1_1") (pintype "passive"))
    )
    (net (code "40") (name "3.3V") (class "Default")
      (node (ref "C35") (pin "2") (pinfunction "2_2") (pintype "passive"))
      (node (ref "C36") (pin "2") (pinfunction "2_2") (pintype "passive"))
      (node (ref "C50") (pin "2") (pinfunction "2_2") (pintype "passive"))
      (node (ref "R101") (pin "2") (pinfunction "2_2") (pintype "passive"))
      (node (ref "R104") (pin "2") (pinfunction "2_2") (pintype "passive"))
      (node (ref "R56") (pin "2") (pinfunction "2_2") (pintype "passive"))
      (node (ref "R57") (pin "2") (pinfunction "2_2") (pintype "passive"))
      (node (ref "R58") (pin "2") (pinfunction "2_2") (pintype "passive"))
      (node (ref "R59") (pin "2") (pinfunction "2_2") (pintype "passive"))
      (node (ref "R60") (pin "2") (pinfunction "2_2") (pintype "passive"))
      (node (ref "R61") (pin "2") (pinfunction "2_2") (pintype "passive"))
      (node (ref "R62") (pin "2") (pinfunction "2_2") (pintype "passive"))
      (node (ref "R63") (pin "2") (pinfunction "2_2") (pintype "passive"))
      (node (ref "R64") (pin "2") (pinfunction "2_2") (pintype "passive"))
      (node (ref "R65") (pin "2") (pinfunction "2_2") (pintype "passive"))
      (node (ref "R66") (pin "2") (pinfunction "2_2") (pintype "passive"))
      (node (ref "R67") (pin "2") (pinfunction "2_2") (pintype "passive"))
      (node (ref "R68") (pin "2") (pinfunction "2_2") (pintype "passive"))
      (node (ref "R69") (pin "2") (pinfunction "2_2") (pintype "passive"))
      (node (ref "R70") (pin "2") (pinfunction "2_2") (pintype "passive"))
      (node (ref "R71") (pin "2") (pinfunction "2_2") (pintype "passive"))
      (node (ref "U6") (pin "11") (pinfunction "A0_11") (pintype "input"))
      (node (ref "U6") (pin "5") (pinfunction "VDD_5") (pintype "power_in"))
    )
    (net (code "41") (name "DC GND") (class "Default")
      (node (ref "C51") (pin "1") (pinfunction "1_1") (pintype "passive"))
      (node (ref "J1") (pin "2") (pinfunction "2_2") (pintype "passive"))
      (node (ref "J3") (pin "2") (pinfunction "2_2") (pintype "passive"))
      (node (ref "R106") (pin "1") (pinfunction "1_1") (pintype "passive"))
    )
    (net (code "42") (name "DC+") (class "Default")
      (node (ref "D1") (pin "K") (pinfunction "K_K") (pintype "passive"))
    )
    (net (code "43") (name "DGND") (class "Default")
      (node (ref "C35") (pin "1") (pinfunction "1_1") (pintype "passive"))
      (node (ref "C36") (pin "1") (pinfunction "1_1") (pintype "passive"))
      (node (ref "C50") (pin "1") (pinfunction "1_1") (pintype "passive"))
      (node (ref "DGND1") (pin "1") (pinfunction "1_1") (pintype "passive"))
      (node (ref "JP4") (pin "1") (pinfunction "1_1") (pintype "passive"))
      (node (ref "JP4") (pin "2") (pinfunction "2_2") (pintype "passive"))
      (node (ref "PC5") (pin "11") (pinfunction "E_11") (pintype "passive"))
      (node (ref "PC5") (pin "13") (pinfunction "E_13") (pintype "passive"))
      (node (ref "PC5") (pin "15") (pinfunction "E_15") (pintype "passive"))
      (node (ref "PC5") (pin "9") (pinfunction "E_9") (pintype "passive"))
      (node (ref "PC6") (pin "11") (pinfunction "E_11") (pintype "passive"))
      (node (ref "PC6") (pin "13") (pinfunction "E_13") (pintype "passive"))
      (node (ref "PC6") (pin "15") (pinfunction "E_15") (pintype "passive"))
      (node (ref "PC6") (pin "9") (pinfunction "E_9") (pintype "passive"))
      (node (ref "PC7") (pin "11") (pinfunction "E_11") (pintype "passive"))
      (node (ref "PC7") (pin "13") (pinfunction "E_13") (pintype "passive"))
      (node (ref "PC7") (pin "15") (pinfunction "E_15") (pintype "passive"))
      (node (ref "PC7") (pin "9") (pinfunction "E_9") (pintype "passive"))
      (node (ref "PC8") (pin "11") (pinfunction "E_11") (pintype "passive"))
      (node (ref "PC8") (pin "13") (pinfunction "E_13") (pintype "passive"))
      (node (ref "PC8") (pin "15") (pinfunction "E_15") (pintype "passive"))
      (node (ref "PC8") (pin "9") (pinfunction "E_9") (pintype "passive"))
      (node (ref "U6") (pin "12") (pinfunction "A1_12") (pintype "input"))
      (node (ref "U6") (pin "13") (pinfunction "A2_13") (pintype "input"))
      (node (ref "U6") (pin "29") (pinfunction "DGND_29") (pintype "passive"))
      (node (ref "U6") (pin "6") (pinfunction "VSS_6") (pintype "power_in"))
    )
    (net (code "44") (name "EX24V") (class "Default")
      (node (ref "C33") (pin "2") (pinfunction "2_2") (pintype "passive"))
      (node (ref "C52") (pin "2") (pinfunction "2_2") (pintype "passive"))
      (node (ref "CN3") (pin "1") (pinfunction "1_1") (pintype "passive"))
      (node (ref "PC5") (pin "1") (pinfunction "A-LED_1") (pintype "passive"))
      (node (ref "PC5") (pin "3") (pinfunction "A-LED_3") (pintype "passive"))
      (node (ref "PC5") (pin "5") (pinfunction "A-LED_5") (pintype "passive"))
      (node (ref "PC5") (pin "7") (pinfunction "A-LED_7") (pintype "passive"))
      (node (ref "PC6") (pin "1") (pinfunction "A-LED_1") (pintype "passive"))
      (node (ref "PC6") (pin "3") (pinfunction "A-LED_3") (pintype "passive"))
      (node (ref "PC6") (pin "5") (pinfunction "A-LED_5") (pintype "passive"))
      (node (ref "PC6") (pin "7") (pinfunction "A-LED_7") (pintype "passive"))
      (node (ref "PC7") (pin "1") (pinfunction "A-LED_1") (pintype "passive"))
      (node (ref "PC7") (pin "3") (pinfunction "A-LED_3") (pintype "passive"))
      (node (ref "PC7") (pin "5") (pinfunction "A-LED_5") (pintype "passive"))
      (node (ref "PC7") (pin "7") (pinfunction "A-LED_7") (pintype "passive"))
      (node (ref "PC8") (pin "1") (pinfunction "A-LED_1") (pintype "passive"))
      (node (ref "PC8") (pin "3") (pinfunction "A-LED_3") (pintype "passive"))
      (node (ref "PC8") (pin "5") (pinfunction "A-LED_5") (pintype "passive"))
      (node (ref "PC8") (pin "7") (pinfunction "A-LED_7") (pintype "passive"))
      (node (ref "R100") (pin "2") (pinfunction "2_2") (pintype "passive"))
      (node (ref "R105") (pin "2") (pinfunction "2_2") (pintype "passive"))
      (node (ref "R72") (pin "2") (pinfunction "2_2") (pintype "passive"))
      (node (ref "R73") (pin "2") (pinfunction "2_2") (pintype "passive"))
      (node (ref "R76") (pin "2") (pinfunction "2_2") (pintype "passive"))
      (node (ref "R77") (pin "2") (pinfunction "2_2") (pintype "passive"))
      (node (ref "R80") (pin "2") (pinfunction "2_2") (pintype "passive"))
      (node (ref "R81") (pin "2") (pinfunction "2_2") (pintype "passive"))
      (node (ref "R84") (pin "2") (pinfunction "2_2") (pintype "passive"))
      (node (ref "R85") (pin "2") (pinfunction "2_2") (pintype "passive"))
      (node (ref "R88") (pin "2") (pinfunction "2_2") (pintype "passive"))
      (node (ref "R89") (pin "2") (pinfunction "2_2") (pintype "passive"))
      (node (ref "R92") (pin "2") (pinfunction "2_2") (pintype "passive"))
      (node (ref "R93") (pin "2") (pinfunction "2_2") (pintype "passive"))
      (node (ref "R96") (pin "2") (pinfunction "2_2") (pintype "passive"))
      (node (ref "R97") (pin "2") (pinfunction "2_2") (pintype "passive"))
    )
    (net (code "45") (name "EXGND") (class "Default")
      (node (ref "C32") (pin "1") (pinfunction "1_1") (pintype "passive"))
      (node (ref "C33") (pin "1") (pinfunction "1_1") (pintype "passive"))
      (node (ref "C34") (pin "1") (pinfunction "1_1") (pintype "passive"))
      (node (ref "C37") (pin "1") (pinfunction "1_1") (pintype "passive"))
      (node (ref "C38") (pin "1") (pinfunction "1_1") (pintype "passive"))
      (node (ref "C39") (pin "1") (pinfunction "1_1") (pintype "passive"))
      (node (ref "C40") (pin "1") (pinfunction "1_1") (pintype "passive"))
      (node (ref "C41") (pin "1") (pinfunction "1_1") (pintype "passive"))
      (node (ref "C42") (pin "1") (pinfunction "1_1") (pintype "passive"))
      (node (ref "C43") (pin "1") (pinfunction "1_1") (pintype "passive"))
      (node (ref "C44") (pin "1") (pinfunction "1_1") (pintype "passive"))
      (node (ref "C45") (pin "1") (pinfunction "1_1") (pintype "passive"))
      (node (ref "C46") (pin "1") (pinfunction "1_1") (pintype "passive"))
      (node (ref "C47") (pin "1") (pinfunction "1_1") (pintype "passive"))
      (node (ref "C48") (pin "1") (pinfunction "1_1") (pintype "passive"))
      (node (ref "C49") (pin "1") (pinfunction "1_1") (pintype "passive"))
      (node (ref "C52") (pin "1") (pinfunction "1_1") (pintype "passive"))
      (node (ref "CN3") (pin "2") (pinfunction "2_2") (pintype "passive"))
      (node (ref "EXT GND1") (pin "1") (pinfunction "1_1") (pintype "passive"))
      (node (ref "J1") (pin "16") (pinfunction "16_16") (pintype "passive"))
      (node (ref "J1") (pin "18") (pinfunction "18_18") (pintype "passive"))
      (node (ref "J3") (pin "12") (pinfunction "12_12") (pintype "passive"))
      (node (ref "JP3") (pin "1") (pinfunction "1_1") (pintype "passive"))
      (node (ref "JP3") (pin "2") (pinfunction "2_2") (pintype "passive"))
      (node (ref "R106") (pin "2") (pinfunction "2_2") (pintype "passive"))
    )
    (net (code "46") (name "Net-(D1-PadA)") (class "Default")
      (node (ref "D1") (pin "A") (pinfunction "A_A") (pintype "passive"))
      (node (ref "FUSE1") (pin "2") (pinfunction "2_2") (pintype "passive"))
    )
    (net (code "47") (name "Net-(PC7-K-LED-Pad8)") (class "Default")
      (node (ref "PC7") (pin "8") (pinfunction "K-LED_8") (pintype "passive"))
      (node (ref "R102") (pin "2") (pinfunction "2_2") (pintype "passive"))
    )
    (net (code "48") (name "Net-(R102-Pad1)") (class "Default")
      (node (ref "R102") (pin "1") (pinfunction "1_1") (pintype "passive"))
      (node (ref "TP1") (pin "1") (pinfunction "1_1") (pintype "passive"))
    )
    (net (code "49") (name "Net-(U6-GPA0)") (class "Default")
      (node (ref "PC6") (pin "10") (pinfunction "C_10") (pintype "passive"))
      (node (ref "R67") (pin "1") (pinfunction "1_1") (pintype "passive"))
      (node (ref "U6") (pin "17") (pinfunction "GPA0_17") (pintype "passive"))
    )
    (net (code "50") (name "Net-(U6-GPA1)") (class "Default")
      (node (ref "PC6") (pin "12") (pinfunction "C_12") (pintype "passive"))
      (node (ref "R66") (pin "1") (pinfunction "1_1") (pintype "passive"))
      (node (ref "U6") (pin "18") (pinfunction "GPA1_18") (pintype "passive"))
    )
    (net (code "51") (name "Net-(U6-GPA2)") (class "Default")
      (node (ref "PC6") (pin "14") (pinfunction "C_14") (pintype "passive"))
      (node (ref "R65") (pin "1") (pinfunction "1_1") (pintype "passive"))
      (node (ref "U6") (pin "19") (pinfunction "GPA2_19") (pintype "passive"))
    )
    (net (code "52") (name "Net-(U6-GPA3)") (class "Default")
      (node (ref "PC6") (pin "16") (pinfunction "C_16") (pintype "passive"))
      (node (ref "R64") (pin "1") (pinfunction "1_1") (pintype "passive"))
      (node (ref "U6") (pin "20") (pinfunction "GPA3_20") (pintype "passive"))
    )
    (net (code "53") (name "Net-(U6-GPA4)") (class "Default")
      (node (ref "PC8") (pin "16") (pinfunction "C_16") (pintype "passive"))
      (node (ref "R68") (pin "1") (pinfunction "1_1") (pintype "passive"))
      (node (ref "U6") (pin "21") (pinfunction "GPA4_21") (pintype "passive"))
    )
    (net (code "54") (name "Net-(U6-GPA5)") (class "Default")
      (node (ref "PC8") (pin "14") (pinfunction "C_14") (pintype "passive"))
      (node (ref "R69") (pin "1") (pinfunction "1_1") (pintype "passive"))
      (node (ref "U6") (pin "22") (pinfunction "GPA5_22") (pintype "passive"))
    )
    (net (code "55") (name "Net-(U6-GPA6)") (class "Default")
      (node (ref "PC8") (pin "12") (pinfunction "C_12") (pintype "passive"))
      (node (ref "R70") (pin "1") (pinfunction "1_1") (pintype "passive"))
      (node (ref "U6") (pin "23") (pinfunction "GPA6_23") (pintype "passive"))
    )
    (net (code "56") (name "Net-(U6-GPA7)") (class "Default")
      (node (ref "PC8") (pin "10") (pinfunction "C_10") (pintype "passive"))
      (node (ref "R71") (pin "1") (pinfunction "1_1") (pintype "passive"))
      (node (ref "U6") (pin "24") (pinfunction "GPA7_24") (pintype "passive"))
    )
    (net (code "57") (name "Net-(U6-GPB0)") (class "Default")
      (node (ref "PC5") (pin "14") (pinfunction "C_14") (pintype "passive"))
      (node (ref "R58") (pin "1") (pinfunction "1_1") (pintype "passive"))
      (node (ref "U6") (pin "25") (pinfunction "GPB0_25") (pintype "passive"))
    )
    (net (code "58") (name "Net-(U6-GPB1)") (class "Default")
      (node (ref "PC5") (pin "16") (pinfunction "C_16") (pintype "passive"))
      (node (ref "R59") (pin "1") (pinfunction "1_1") (pintype "passive"))
      (node (ref "U6") (pin "26") (pinfunction "GPB1_26") (pintype "passive"))
    )
    (net (code "59") (name "Net-(U6-GPB2)") (class "Default")
      (node (ref "PC5") (pin "12") (pinfunction "C_12") (pintype "passive"))
      (node (ref "R57") (pin "1") (pinfunction "1_1") (pintype "passive"))
      (node (ref "U6") (pin "27") (pinfunction "GPB2_27") (pintype "passive"))
    )
    (net (code "60") (name "Net-(U6-GPB3)") (class "Default")
      (node (ref "PC5") (pin "10") (pinfunction "C_10") (pintype "passive"))
      (node (ref "R56") (pin "1") (pinfunction "1_1") (pintype "passive"))
      (node (ref "U6") (pin "28") (pinfunction "GPB3_28") (pintype "passive"))
    )
    (net (code "61") (name "Net-(U6-GPB4)") (class "Default")
      (node (ref "PC7") (pin "16") (pinfunction "C_16") (pintype "passive"))
      (node (ref "R63") (pin "1") (pinfunction "1_1") (pintype "passive"))
      (node (ref "U6") (pin "1") (pinfunction "GPB4_1") (pintype "passive"))
    )
    (net (code "62") (name "Net-(U6-GPB5)") (class "Default")
      (node (ref "PC7") (pin "14") (pinfunction "C_14") (pintype "passive"))
      (node (ref "R62") (pin "1") (pinfunction "1_1") (pintype "passive"))
      (node (ref "U6") (pin "2") (pinfunction "GPB5_2") (pintype "passive"))
    )
    (net (code "63") (name "Net-(U6-GPB6)") (class "Default")
      (node (ref "PC7") (pin "12") (pinfunction "C_12") (pintype "passive"))
      (node (ref "R61") (pin "1") (pinfunction "1_1") (pintype "passive"))
      (node (ref "U6") (pin "3") (pinfunction "GPB6_3") (pintype "passive"))
    )
    (net (code "64") (name "Net-(U6-GPB7)") (class "Default")
      (node (ref "PC7") (pin "10") (pinfunction "C_10") (pintype "passive"))
      (node (ref "R60") (pin "1") (pinfunction "1_1") (pintype "passive"))
      (node (ref "U6") (pin "4") (pinfunction "GPB7_4") (pintype "passive"))
    )
    (net (code "65") (name "unconnected-(U6-ITB-Pad15)") (class "Default")
      (node (ref "U6") (pin "15") (pinfunction "ITB_15") (pintype "output+no_connect"))
    )
    (net (code "66") (name "unconnected-(U6-NC-Pad7)") (class "Default")
      (node (ref "U6") (pin "7") (pinfunction "NC_7") (pintype "passive+no_connect"))
    )
    (net (code "67") (name "unconnected-(U6-NC-Pad10)") (class "Default")
      (node (ref "U6") (pin "10") (pinfunction "NC_10") (pintype "passive+no_connect"))
    )
  )
)
